# haasoscope_triggerout_board.net
KiCad netlist of a schematic drawn in EAGLE
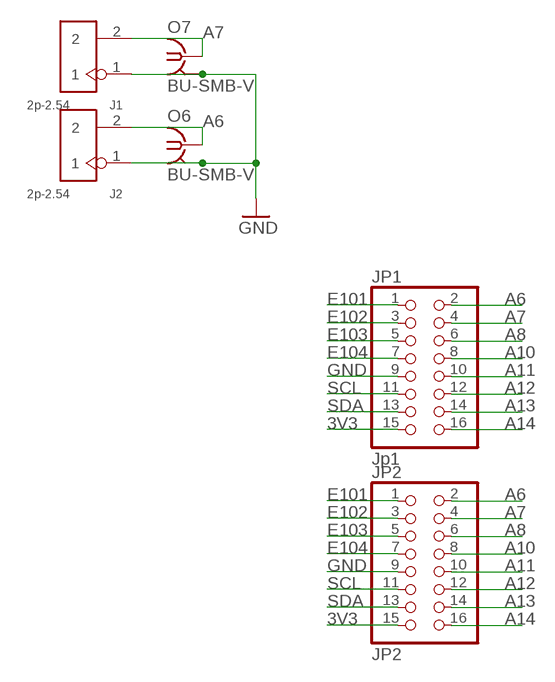
[diagram p0: schematic, sheet 1]

(export (version "E")
  (design (tool "Eeschema 10.0.6"))
  (components
    (comp (ref "J1")
      (value "2p-2.54")
      (footprint "eagle-import:H2-2.54")
      (fields (field (name "MPN") "P125-1102A0BS116A1"))
      (libsource (lib "eagle-import") (part "DIP-BLACK-MALE-HEADER-VERT(2P-2.54)"))
    )
    (comp (ref "J2")
      (value "2p-2.54")
      (footprint "eagle-import:H2-2.54")
      (fields (field (name "MPN") "P125-1102A0BS116A1"))
      (libsource (lib "eagle-import") (part "DIP-BLACK-MALE-HEADER-VERT(2P-2.54)"))
    )
    (comp (ref "JP1")
      (value "Jp1")
      (footprint "eagle-import:2X08")
      (libsource (lib "eagle-import") (part "PINHD-2X8"))
    )
    (comp (ref "JP2")
      (value "JP2")
      (footprint "eagle-import:2X08")
      (libsource (lib "eagle-import") (part "PINHD-2X8"))
    )
    (comp (ref "O6")
      (value "BU-SMB-V")
      (footprint "eagle-import:BU-SMB-V")
      (libsource (lib "eagle-import") (part "BU-SMB-V"))
    )
    (comp (ref "O7")
      (value "BU-SMB-V")
      (footprint "eagle-import:BU-SMB-V")
      (libsource (lib "eagle-import") (part "BU-SMB-V"))
    )
  )
  (nets
    (net (code "1") (name "/3V3") (class "Default")
      (node (ref "JP1") (pin "15") (pinfunction "15_15") (pintype "passive"))
      (node (ref "JP2") (pin "15") (pinfunction "15_15") (pintype "passive"))
    )
    (net (code "2") (name "/A6") (class "Default")
      (node (ref "J2") (pin "2") (pinfunction "2_2") (pintype "bidirectional"))
      (node (ref "JP1") (pin "2") (pinfunction "2_2") (pintype "passive"))
      (node (ref "JP2") (pin "2") (pinfunction "2_2") (pintype "passive"))
      (node (ref "O6") (pin "1") (pinfunction "1_1") (pintype "passive"))
    )
    (net (code "3") (name "/A7") (class "Default")
      (node (ref "J1") (pin "2") (pinfunction "2_2") (pintype "bidirectional"))
      (node (ref "JP1") (pin "4") (pinfunction "4_4") (pintype "passive"))
      (node (ref "JP2") (pin "4") (pinfunction "4_4") (pintype "passive"))
      (node (ref "O7") (pin "1") (pinfunction "1_1") (pintype "passive"))
    )
    (net (code "4") (name "/A8") (class "Default")
      (node (ref "JP1") (pin "6") (pinfunction "6_6") (pintype "passive"))
      (node (ref "JP2") (pin "6") (pinfunction "6_6") (pintype "passive"))
    )
    (net (code "5") (name "/A10") (class "Default")
      (node (ref "JP1") (pin "8") (pinfunction "8_8") (pintype "passive"))
      (node (ref "JP2") (pin "8") (pinfunction "8_8") (pintype "passive"))
    )
    (net (code "6") (name "/A11") (class "Default")
      (node (ref "JP1") (pin "10") (pinfunction "10_10") (pintype "passive"))
      (node (ref "JP2") (pin "10") (pinfunction "10_10") (pintype "passive"))
    )
    (net (code "7") (name "/A12") (class "Default")
      (node (ref "JP1") (pin "12") (pinfunction "12_12") (pintype "passive"))
      (node (ref "JP2") (pin "12") (pinfunction "12_12") (pintype "passive"))
    )
    (net (code "8") (name "/A13") (class "Default")
      (node (ref "JP1") (pin "14") (pinfunction "14_14") (pintype "passive"))
      (node (ref "JP2") (pin "14") (pinfunction "14_14") (pintype "passive"))
    )
    (net (code "9") (name "/A14") (class "Default")
      (node (ref "JP1") (pin "16") (pinfunction "16_16") (pintype "passive"))
      (node (ref "JP2") (pin "16") (pinfunction "16_16") (pintype "passive"))
    )
    (net (code "10") (name "/E101") (class "Default")
      (node (ref "JP1") (pin "1") (pinfunction "1_1") (pintype "passive"))
      (node (ref "JP2") (pin "1") (pinfunction "1_1") (pintype "passive"))
    )
    (net (code "11") (name "/E102") (class "Default")
      (node (ref "JP1") (pin "3") (pinfunction "3_3") (pintype "passive"))
      (node (ref "JP2") (pin "3") (pinfunction "3_3") (pintype "passive"))
    )
    (net (code "12") (name "/E103") (class "Default")
      (node (ref "JP1") (pin "5") (pinfunction "5_5") (pintype "passive"))
      (node (ref "JP2") (pin "5") (pinfunction "5_5") (pintype "passive"))
    )
    (net (code "13") (name "/E104") (class "Default")
      (node (ref "JP1") (pin "7") (pinfunction "7_7") (pintype "passive"))
      (node (ref "JP2") (pin "7") (pinfunction "7_7") (pintype "passive"))
    )
    (net (code "14") (name "/SCL") (class "Default")
      (node (ref "JP1") (pin "11") (pinfunction "11_11") (pintype "passive"))
      (node (ref "JP2") (pin "11") (pinfunction "11_11") (pintype "passive"))
    )
    (net (code "15") (name "/SDA") (class "Default")
      (node (ref "JP1") (pin "13") (pinfunction "13_13") (pintype "passive"))
      (node (ref "JP2") (pin "13") (pinfunction "13_13") (pintype "passive"))
    )
    (net (code "16") (name "GND") (class "Default")
      (node (ref "J1") (pin "1") (pinfunction "1_1") (pintype "bidirectional"))
      (node (ref "J2") (pin "1") (pinfunction "1_1") (pintype "bidirectional"))
      (node (ref "JP1") (pin "9") (pinfunction "9_9") (pintype "passive"))
      (node (ref "JP2") (pin "9") (pinfunction "9_9") (pintype "passive"))
      (node (ref "O6") (pin "2") (pinfunction "2_2") (pintype "passive"))
      (node (ref "O6") (pin "3") (pinfunction "2_3") (pintype "passive"))
      (node (ref "O6") (pin "4") (pinfunction "2_4") (pintype "passive"))
      (node (ref "O6") (pin "5") (pinfunction "2_5") (pintype "passive"))
      (node (ref "O7") (pin "2") (pinfunction "2_2") (pintype "passive"))
      (node (ref "O7") (pin "3") (pinfunction "2_3") (pintype "passive"))
      (node (ref "O7") (pin "4") (pinfunction "2_4") (pintype "passive"))
      (node (ref "O7") (pin "5") (pinfunction "2_5") (pintype "passive"))
    )
  )
)
